# HandBox-KCTW.net
KiCad netlist of a schematic drawn in Altium Designer
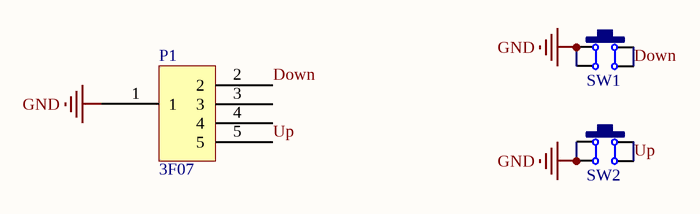
[diagram p0: HandBox-KCTW.SchDoc]

(export (version "E")
  (design (tool "Eeschema 10.0.6"))
  (components
    (comp (ref "P1")
      (value "3F07")
      (footprint "3F07")
      (description "EarPhone3.5")
      (libsource (lib "SS") (part "3F07"))
    )
    (comp (ref "SW1")
      (value "6x6x5")
      (footprint "TSW SMD-12*12*8")
      (description "贴片6x6轻触开关")
      (fields (field (name "版权归属") "源创客"))
      (libsource (lib "5.1   - 按键-开关") (part "TSW SMD-6x6"))
    )
    (comp (ref "SW2")
      (value "6x6x5")
      (footprint "TSW SMD-12*12*8")
      (description "贴片6x6轻触开关")
      (fields (field (name "版权归属") "源创客"))
      (libsource (lib "5.1   - 按键-开关") (part "TSW SMD-6x6"))
    )
  )
  (nets
    (net (code "1") (name "/Down") (class "Default")
      (node (ref "P1") (pin "2") (pinfunction "2_2") (pintype "passive"))
      (node (ref "SW1") (pin "2") (pinfunction "2_2") (pintype "passive"))
      (node (ref "SW1") (pin "3") (pinfunction "3_3") (pintype "passive"))
    )
    (net (code "2") (name "/Up") (class "Default")
      (node (ref "P1") (pin "5") (pinfunction "5_5") (pintype "passive"))
      (node (ref "SW2") (pin "2") (pinfunction "2_2") (pintype "passive"))
      (node (ref "SW2") (pin "3") (pinfunction "3_3") (pintype "passive"))
    )
    (net (code "3") (name "GND") (class "Default")
      (node (ref "P1") (pin "1") (pinfunction "1_1") (pintype "passive"))
      (node (ref "SW1") (pin "1") (pinfunction "1_1") (pintype "passive"))
      (node (ref "SW1") (pin "4") (pinfunction "4_4") (pintype "passive"))
      (node (ref "SW2") (pin "1") (pinfunction "1_1") (pintype "passive"))
      (node (ref "SW2") (pin "4") (pinfunction "4_4") (pintype "passive"))
    )
    (net (code "4") (name "unconnected-(P1-Pad3)") (class "Default")
      (node (ref "P1") (pin "3") (pinfunction "3_3") (pintype "passive"))
    )
    (net (code "5") (name "unconnected-(P1-Pad4)") (class "Default")
      (node (ref "P1") (pin "4") (pinfunction "4_4") (pintype "passive"))
    )
  )
)
